# CPU_Module.net
KiCad netlist of a schematic drawn in Altium Designer
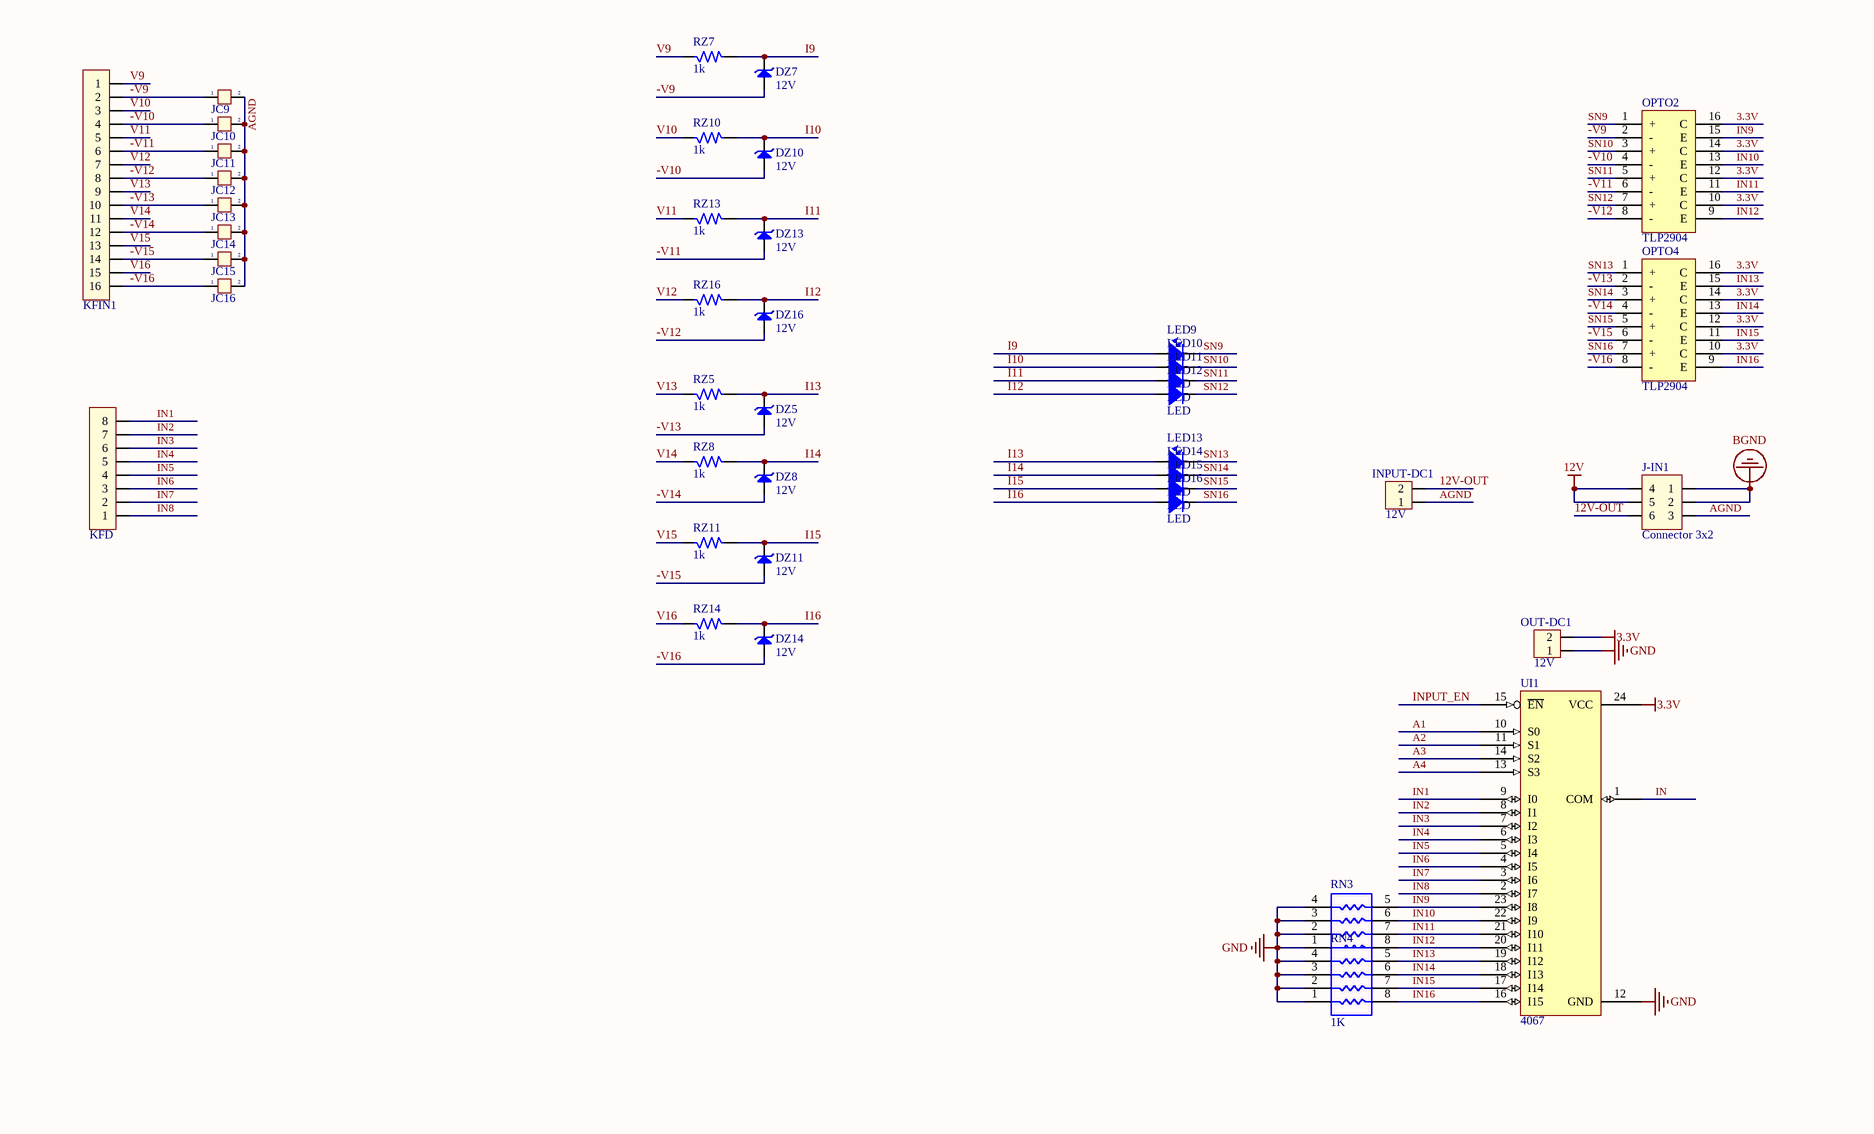
[diagram p0: CPU Module.SchDoc, top]
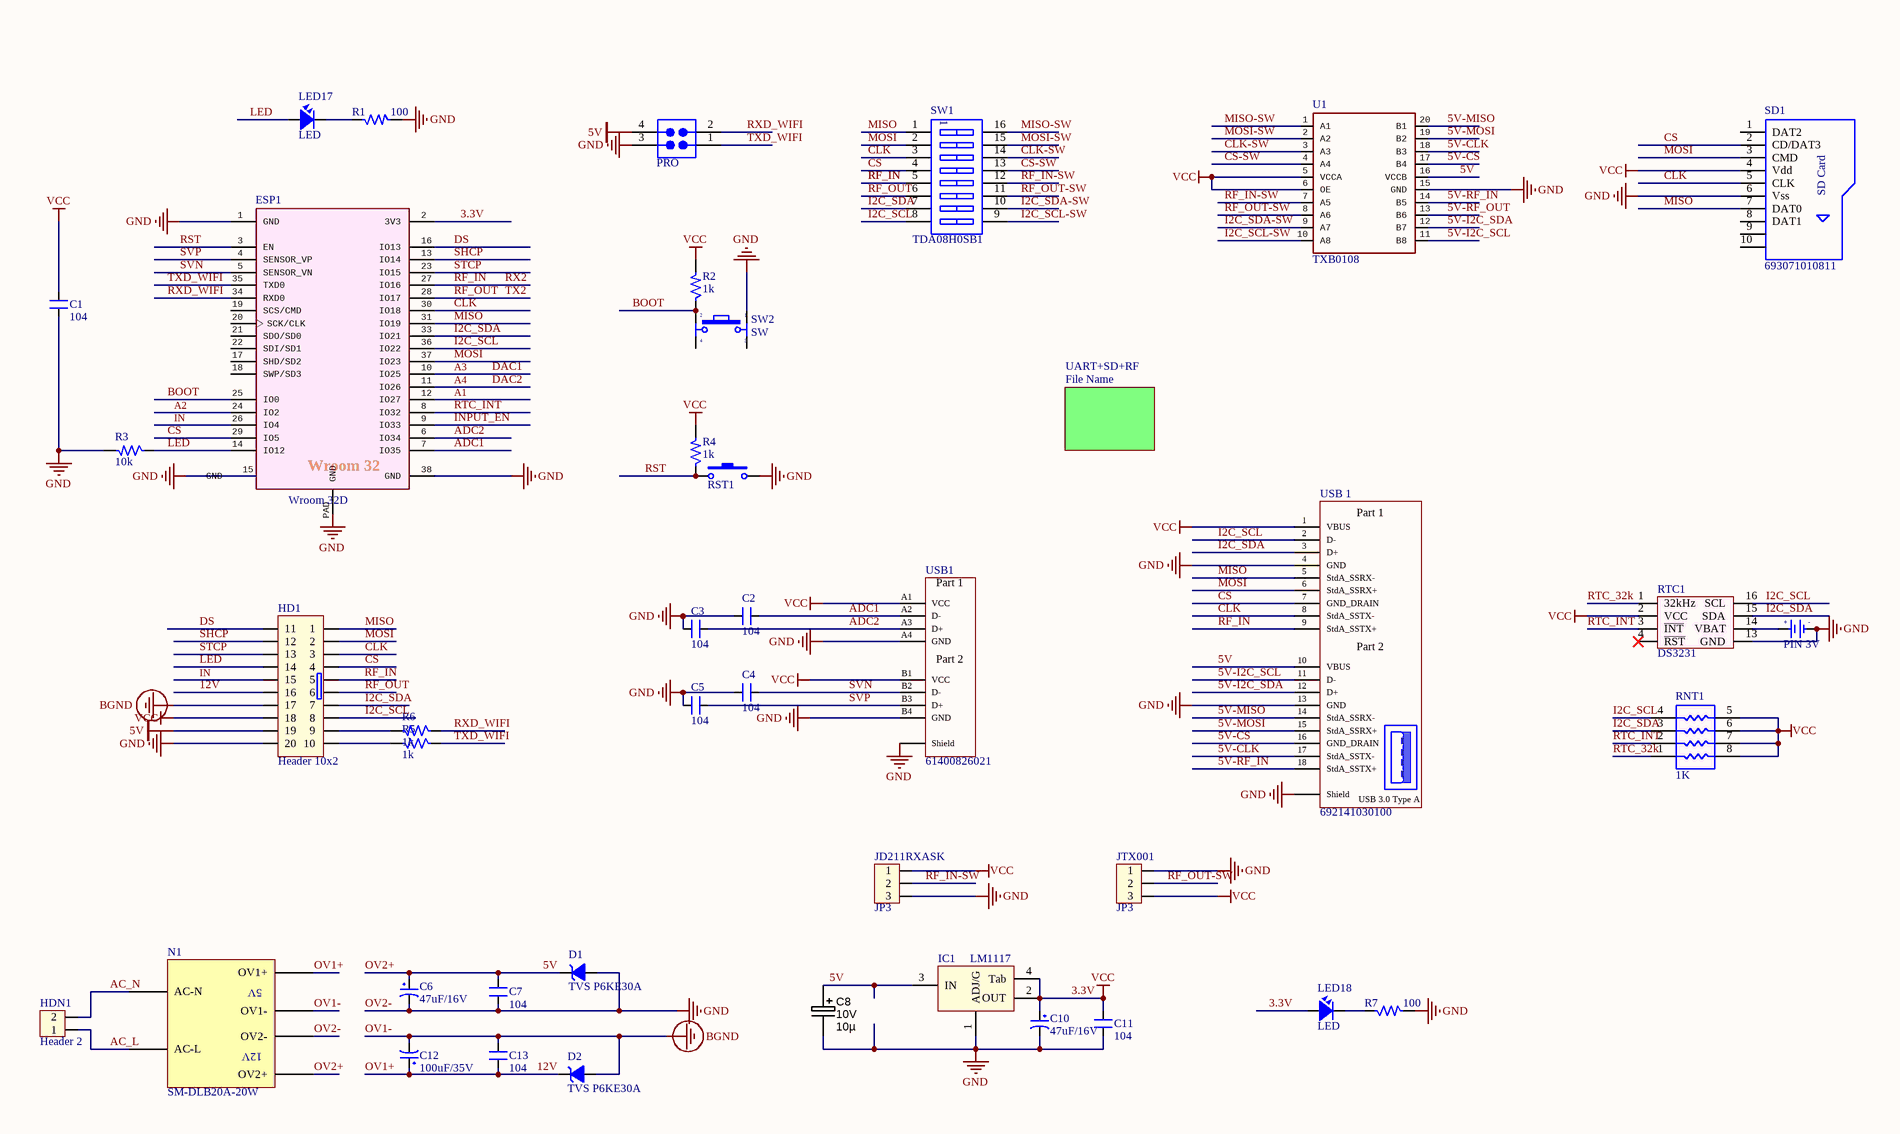
[diagram p1: CPU Module.SchDoc, bottom]

(export (version "E")
  (design (tool "Eeschema 10.0.6"))
  (components
    (comp (ref "BT1")
      (value "PIN 3V")
      (footprint "PIN CR1220-SMD")
      (description "Lithium Battery Holder for CR2032 3V Cell")
      (libsource (lib "Library") (part "PIN 3V"))
    )
    (comp (ref "C1")
      (value "104")
      (footprint "SM-0805")
      (description "Cap SMD")
      (libsource (lib "syhaunguyen") (part "CM"))
    )
    (comp (ref "C2")
      (value "104")
      (footprint "SM-0805")
      (description "Cap SMD")
      (libsource (lib "syhaunguyen") (part "CM"))
    )
    (comp (ref "C3")
      (value "104")
      (footprint "SM-0805")
      (description "Cap SMD")
      (libsource (lib "syhaunguyen") (part "CM"))
    )
    (comp (ref "C4")
      (value "104")
      (footprint "SM-0805")
      (description "Cap SMD")
      (libsource (lib "syhaunguyen") (part "CM"))
    )
    (comp (ref "C5")
      (value "104")
      (footprint "SM-0805")
      (description "Cap SMD")
      (libsource (lib "syhaunguyen") (part "CM"))
    )
    (comp (ref "C6")
      (value "47uF/16V")
      (footprint "WCAP-AS5H_6.3x5.5")
      (description "Cap 100uF/35V - 470uF/16V")
      (libsource (lib "syhaunguyen") (part "CP3"))
    )
    (comp (ref "C7")
      (value "104")
      (footprint "SM-0805")
      (description "Cap SMD")
      (libsource (lib "syhaunguyen") (part "CM"))
    )
    (comp (ref "C8")
      (value "10µ")
      (footprint "CAPMP3216X180N")
      (description "Capacitor SMD Tantalum 10uF 20% 10V 0805")
      (fields (field (name "TOLERANCE") "±20%") (field (name "RATINGS") "10V"))
      (libsource (lib "PBL - Capacitors") (part "CAPT_10u_0805_10V"))
    )
    (comp (ref "C10")
      (value "47uF/16V")
      (footprint "WCAP-AS5H_6.3x5.5")
      (description "Cap 100uF/35V - 470uF/16V")
      (libsource (lib "") (part "CP3_1"))
    )
    (comp (ref "C11")
      (value "104")
      (footprint "SM-0805")
      (description "Cap SMD")
      (libsource (lib "syhaunguyen") (part "CM"))
    )
    (comp (ref "C12")
      (value "100uF/35V")
      (footprint "WCAP-AS5H_8x10.5")
      (description "Cap 100uF/35V - 470uF/16V")
      (libsource (lib "syhaunguyen") (part "CP3"))
    )
    (comp (ref "C13")
      (value "104")
      (footprint "SM-0805")
      (description "Cap SMD")
      (libsource (lib "syhaunguyen") (part "CM"))
    )
    (comp (ref "D1")
      (value "TVS P6KE30A")
      (footprint "DO-214AA_Unidirectional")
      (description "Diode Zenner")
      (libsource (lib "syhaunguyen") (part "DZ"))
    )
    (comp (ref "D2")
      (value "TVS P6KE30A")
      (footprint "DO-214AA_Unidirectional")
      (description "Diode Zenner")
      (libsource (lib "syhaunguyen") (part "DZ"))
    )
    (comp (ref "DZ5")
      (value "12V")
      (footprint "DIOS 1S2P1406H")
      (description "DIODE GEN PURP 75V 200MA LLDS")
      (libsource (lib "Diode") (part "DIODE Zener"))
    )
    (comp (ref "DZ7")
      (value "12V")
      (footprint "DIOS 1S2P1406H")
      (description "DIODE GEN PURP 75V 200MA LLDS")
      (libsource (lib "Diode") (part "DIODE Zener"))
    )
    (comp (ref "DZ8")
      (value "12V")
      (footprint "DIOS 1S2P1406H")
      (description "DIODE GEN PURP 75V 200MA LLDS")
      (libsource (lib "Diode") (part "DIODE Zener"))
    )
    (comp (ref "DZ10")
      (value "12V")
      (footprint "DIOS 1S2P1406H")
      (description "DIODE GEN PURP 75V 200MA LLDS")
      (libsource (lib "Diode") (part "DIODE Zener"))
    )
    (comp (ref "DZ11")
      (value "12V")
      (footprint "DIOS 1S2P1406H")
      (description "DIODE GEN PURP 75V 200MA LLDS")
      (libsource (lib "Diode") (part "DIODE Zener"))
    )
    (comp (ref "DZ13")
      (value "12V")
      (footprint "DIOS 1S2P1406H")
      (description "DIODE GEN PURP 75V 200MA LLDS")
      (libsource (lib "Diode") (part "DIODE Zener"))
    )
    (comp (ref "DZ14")
      (value "12V")
      (footprint "DIOS 1S2P1406H")
      (description "DIODE GEN PURP 75V 200MA LLDS")
      (libsource (lib "Diode") (part "DIODE Zener"))
    )
    (comp (ref "DZ16")
      (value "12V")
      (footprint "DIOS 1S2P1406H")
      (description "DIODE GEN PURP 75V 200MA LLDS")
      (libsource (lib "Diode") (part "DIODE Zener"))
    )
    (comp (ref "ESP1")
      (value "Wroom 32D")
      (footprint "MODULE_ESP-WROOM-32")
      (fields (field (name "MF") "Olimex LTD") (field (name "MP") "ESP-WROOM-32"))
      (libsource (lib "ESP-WROOM-32") (part "ESP-WROOM-32"))
    )
    (comp (ref "HD1")
      (value "Header 10x2")
      (footprint "Hed2X10S")
      (libsource (lib "syhaunguyen") (part "HED10X2"))
    )
    (comp (ref "HDN1")
      (value "Header 2")
      (footprint "KF211V- 2")
      (description "Header 2 (Green)")
      (libsource (lib "syhaunguyen") (part "Hed2"))
    )
    (comp (ref "IC1")
      (value "LM1117")
      (footprint "SOT223-4N")
      (description "3v3")
      (libsource (lib "syhaunguyen") (part "LM1117"))
    )
    (comp (ref "INPUT-DC1")
      (value "12V")
      (footprint "KF211V- 2")
      (description "Header 2 (Green)")
      (libsource (lib "syhaunguyen") (part "Hed2"))
    )
    (comp (ref "J-IN1")
      (value "Connector 3x2")
      (footprint "JP3x2")
      (libsource (lib "syhaunguyen") (part "JP3x2"))
    )
    (comp (ref "JC9") (value "Jumper 2") (footprint "JP2") (libsource (lib "syhaunguyen") (part "JP 2")))
    (comp (ref "JC10") (value "Jumper 2") (footprint "JP2") (libsource (lib "syhaunguyen") (part "JP 2")))
    (comp (ref "JC11") (value "Jumper 2") (footprint "JP2") (libsource (lib "syhaunguyen") (part "JP 2")))
    (comp (ref "JC12") (value "Jumper 2") (footprint "JP2") (libsource (lib "syhaunguyen") (part "JP 2")))
    (comp (ref "JC13") (value "Jumper 2") (footprint "JP2") (libsource (lib "syhaunguyen") (part "JP 2")))
    (comp (ref "JC14") (value "Jumper 2") (footprint "JP2") (libsource (lib "syhaunguyen") (part "JP 2")))
    (comp (ref "JC15") (value "Jumper 2") (footprint "JP2") (libsource (lib "syhaunguyen") (part "JP 2")))
    (comp (ref "JC16") (value "Jumper 2") (footprint "JP2") (libsource (lib "syhaunguyen") (part "JP 2")))
    (comp (ref "JD211RXASK")
      (value "JP3")
      (footprint "JP3")
      (description "Connector 3")
      (libsource (lib "syhaunguyen") (part "Con3"))
    )
    (comp (ref "JTX001")
      (value "JP3")
      (footprint "JP3")
      (description "Connector 3")
      (libsource (lib "syhaunguyen") (part "Con3"))
    )
    (comp (ref "KFD")
      (value "Header 8")
      (footprint "KF211V- 8")
      (description "KF211R-5.0")
      (libsource (lib "Sonbui") (part "KF 8"))
    )
    (comp (ref "KFIN1")
      (value "Header 16")
      (footprint "KF211V- 16")
      (description "KF211R-5.0")
      (libsource (lib "Sonbui") (part "KF 16"))
    )
    (comp (ref "LED9")
      (value "LED")
      (footprint "LED0805")
      (description "LED Single colour Green and Red")
      (libsource (lib "syhaunguyen") (part "LED"))
    )
    (comp (ref "LED10")
      (value "LED")
      (footprint "LED0805")
      (description "LED Single colour Green and Red")
      (libsource (lib "syhaunguyen") (part "LED"))
    )
    (comp (ref "LED11")
      (value "LED")
      (footprint "LED0805")
      (description "LED Single colour Green and Red")
      (libsource (lib "syhaunguyen") (part "LED"))
    )
    (comp (ref "LED12")
      (value "LED")
      (footprint "LED0805")
      (description "LED Single colour Green and Red")
      (libsource (lib "syhaunguyen") (part "LED"))
    )
    (comp (ref "LED13")
      (value "LED")
      (footprint "LED0805")
      (description "LED Single colour Green and Red")
      (libsource (lib "syhaunguyen") (part "LED"))
    )
    (comp (ref "LED14")
      (value "LED")
      (footprint "LED0805")
      (description "LED Single colour Green and Red")
      (libsource (lib "syhaunguyen") (part "LED"))
    )
    (comp (ref "LED15")
      (value "LED")
      (footprint "LED0805")
      (description "LED Single colour Green and Red")
      (libsource (lib "syhaunguyen") (part "LED"))
    )
    (comp (ref "LED16")
      (value "LED")
      (footprint "LED0805")
      (description "LED Single colour Green and Red")
      (libsource (lib "syhaunguyen") (part "LED"))
    )
    (comp (ref "LED17")
      (value "LED")
      (footprint "LED0805")
      (description "LED Single colour Green and Red")
      (libsource (lib "syhaunguyen") (part "LED"))
    )
    (comp (ref "LED18")
      (value "LED")
      (footprint "LED0805")
      (description "LED Single colour Green and Red")
      (libsource (lib "syhaunguyen") (part "LED"))
    )
    (comp (ref "N1")
      (value "SM-DLB20A-20W")
      (footprint "SM-DLB20A")
      (libsource (lib "AC-DC Module") (part "SM-DLB20A-20W"))
    )
    (comp (ref "OPTO2")
      (value "TLP2904")
      (footprint "SO-16")
      (description "PC817 OPTO")
      (libsource (lib "Cty1") (part "PC817 x 4"))
    )
    (comp (ref "OPTO4")
      (value "TLP2904")
      (footprint "SO-16")
      (description "PC817 OPTO")
      (libsource (lib "Cty1") (part "PC817 x 4"))
    )
    (comp (ref "OUT-DC1")
      (value "12V")
      (footprint "KF211V- 2")
      (description "Header 2 (Green)")
      (libsource (lib "syhaunguyen") (part "Hed2"))
    )
    (comp (ref "PRO")
      (value "61300421821")
      (footprint "61300421121")
      (description "2.54 mm Dual Socket Header, 04p")
      (fields (field (name "PUBLISHER") "Wurth Elektronik"))
      (libsource (lib "JUMPER") (part "JP2x2 2.54MM"))
    )
    (comp (ref "R1")
      (value "100")
      (footprint "R-0805")
      (description "Resistor 1/4W")
      (libsource (lib "heromap") (part "R"))
    )
    (comp (ref "R2")
      (value "1k")
      (footprint "R-0805")
      (description "Resistor 1/4W")
      (libsource (lib "heromap") (part "R"))
    )
    (comp (ref "R3")
      (value "10k")
      (footprint "R-0805")
      (description "Resistor 1/4W")
      (libsource (lib "heromap") (part "R"))
    )
    (comp (ref "R4")
      (value "1k")
      (footprint "R-0805")
      (description "Resistor 1/4W")
      (libsource (lib "heromap") (part "R"))
    )
    (comp (ref "R5")
      (value "1k")
      (footprint "R-0805")
      (description "Resistor 1/4W")
      (libsource (lib "heromap") (part "R"))
    )
    (comp (ref "R6")
      (value "1k")
      (footprint "R-0805")
      (description "Resistor 1/4W")
      (libsource (lib "heromap") (part "R"))
    )
    (comp (ref "R7")
      (value "100")
      (footprint "R-0805")
      (description "Resistor 1/4W")
      (libsource (lib "heromap") (part "R"))
    )
    (comp (ref "RN3")
      (value "1K")
      (footprint "RES P4 Dual 0805/2012")
      (libsource (lib "Resistor") (part "Respack 4 Dual"))
    )
    (comp (ref "RN4")
      (value "1K")
      (footprint "RES P4 Dual 0805/2012")
      (libsource (lib "Resistor") (part "Respack 4 Dual"))
    )
    (comp (ref "RNT1")
      (value "1K")
      (footprint "RES P4 Dual 0805/2012")
      (libsource (lib "Resistor") (part "Respack 4 Dual"))
    )
    (comp (ref "RST1")
      (value "SW-SMD")
      (footprint "SW-SMD")
      (description "Switch")
      (fields (field (name "PUBLISHER") "Altium Limited"))
      (libsource (lib "Schematic") (part "SW-SMD"))
    )
    (comp (ref "RTC1")
      (value "DS3231")
      (footprint "SOIC127P750X1030-16N")
      (description "I2C RTC/TCXO/Crystal")
      (libsource (lib "Ics") (part "DS3231"))
    )
    (comp (ref "RZ5")
      (value "1k")
      (footprint "SM-1206")
      (description "Resistor 1/4W")
      (libsource (lib "syhaunguyen") (part "R"))
    )
    (comp (ref "RZ7")
      (value "1k")
      (footprint "SM-1206")
      (description "Resistor 1/4W")
      (libsource (lib "syhaunguyen") (part "R"))
    )
    (comp (ref "RZ8")
      (value "1k")
      (footprint "SM-1206")
      (description "Resistor 1/4W")
      (libsource (lib "syhaunguyen") (part "R"))
    )
    (comp (ref "RZ10")
      (value "1k")
      (footprint "SM-1206")
      (description "Resistor 1/4W")
      (libsource (lib "syhaunguyen") (part "R"))
    )
    (comp (ref "RZ11")
      (value "1k")
      (footprint "SM-1206")
      (description "Resistor 1/4W")
      (libsource (lib "syhaunguyen") (part "R"))
    )
    (comp (ref "RZ13")
      (value "1k")
      (footprint "SM-1206")
      (description "Resistor 1/4W")
      (libsource (lib "syhaunguyen") (part "R"))
    )
    (comp (ref "RZ14")
      (value "1k")
      (footprint "SM-1206")
      (description "Resistor 1/4W")
      (libsource (lib "syhaunguyen") (part "R"))
    )
    (comp (ref "RZ16")
      (value "1k")
      (footprint "SM-1206")
      (description "Resistor 1/4W")
      (libsource (lib "syhaunguyen") (part "R"))
    )
    (comp (ref "SD1")
      (value "693071010811")
      (footprint "693071010811")
      (description "Micro SD Card Connector Push & Push - 8 pins")
      (fields (field (name "PUBLISHER") "Wurth Elektronik"))
      (libsource (lib "Card") (part "SD-693071010811"))
    )
    (comp (ref "SW1")
      (value "TDA08H0SB1")
      (footprint "SW8-416131160808")
      (description "WS-DITV 2.54 mm small compact THT with raised actuator, 8p")
      (fields (field (name "PART NUMBER") "418127270908") (field (name "PUBLISHER") "Wurth Elektronik"))
      (libsource (lib "Switch") (part "SW 8P"))
    )
    (comp (ref "SW2")
      (value "SW")
      (footprint "SW2-D2")
      (description "Switch button 4 pin")
      (libsource (lib "ESP8266_CD4051") (part "SW4"))
    )
    (comp (ref "U1")
      (value "TXB0108")
      (footprint "TSSOP65P440X650-20N")
      (fields (field (name "MF") "Texas Instruments"))
      (libsource (lib "TXB0108") (part "TXB0108"))
    )
    (comp (ref "UI1")
      (value "4067")
      (footprint "SSOP65P530X850-24N")
      (description "MUX-74HC4067")
      (libsource (lib "CustomLibrary") (part "MUX-74HC4067"))
    )
    (comp (ref "USB 1")
      (value "692141030100")
      (footprint "692141030100")
      (description "USB 3.0 Type A")
      (fields (field (name "PUBLISHER") "Wurth Elektronik"))
      (libsource (lib "Usb") (part "USB 3.0 Type A Female THR Stacked"))
    )
    (comp (ref "USB1")
      (value "61400826021")
      (footprint "61400826021")
      (description "USB 2.0 Type A Female THR Stacked")
      (fields (field (name "PUBLISHER") "Wurth Elektronik"))
      (libsource (lib "Usb") (part "USB 2.0 Type A Female THR Stacked"))
    )
  )
  (nets
    (net (code "1") (name "/-V9") (class "Default")
      (node (ref "DZ7") (pin "1") (pinfunction "A_1") (pintype "passive"))
      (node (ref "JC9") (pin "1") (pinfunction "1_1") (pintype "passive"))
      (node (ref "KFIN1") (pin "2") (pinfunction "2_2") (pintype "passive"))
      (node (ref "OPTO2") (pin "2") (pinfunction "-_2") (pintype "passive"))
    )
    (net (code "2") (name "/-V10") (class "Default")
      (node (ref "DZ10") (pin "1") (pinfunction "A_1") (pintype "passive"))
      (node (ref "JC10") (pin "1") (pinfunction "1_1") (pintype "passive"))
      (node (ref "KFIN1") (pin "4") (pinfunction "4_4") (pintype "passive"))
      (node (ref "OPTO2") (pin "4") (pinfunction "-_4") (pintype "passive"))
    )
    (net (code "3") (name "/-V11") (class "Default")
      (node (ref "DZ13") (pin "1") (pinfunction "A_1") (pintype "passive"))
      (node (ref "JC11") (pin "1") (pinfunction "1_1") (pintype "passive"))
      (node (ref "KFIN1") (pin "6") (pinfunction "6_6") (pintype "passive"))
      (node (ref "OPTO2") (pin "6") (pinfunction "-_6") (pintype "passive"))
    )
    (net (code "4") (name "/-V12") (class "Default")
      (node (ref "DZ16") (pin "1") (pinfunction "A_1") (pintype "passive"))
      (node (ref "JC12") (pin "1") (pinfunction "1_1") (pintype "passive"))
      (node (ref "KFIN1") (pin "8") (pinfunction "8_8") (pintype "passive"))
      (node (ref "OPTO2") (pin "8") (pinfunction "-_8") (pintype "passive"))
    )
    (net (code "5") (name "/-V13") (class "Default")
      (node (ref "DZ5") (pin "1") (pinfunction "A_1") (pintype "passive"))
      (node (ref "JC13") (pin "1") (pinfunction "1_1") (pintype "passive"))
      (node (ref "KFIN1") (pin "10") (pinfunction "10_10") (pintype "passive"))
      (node (ref "OPTO4") (pin "2") (pinfunction "-_2") (pintype "passive"))
    )
    (net (code "6") (name "/-V14") (class "Default")
      (node (ref "DZ8") (pin "1") (pinfunction "A_1") (pintype "passive"))
      (node (ref "JC14") (pin "1") (pinfunction "1_1") (pintype "passive"))
      (node (ref "KFIN1") (pin "12") (pinfunction "12_12") (pintype "passive"))
      (node (ref "OPTO4") (pin "4") (pinfunction "-_4") (pintype "passive"))
    )
    (net (code "7") (name "/-V15") (class "Default")
      (node (ref "DZ11") (pin "1") (pinfunction "A_1") (pintype "passive"))
      (node (ref "JC15") (pin "1") (pinfunction "1_1") (pintype "passive"))
      (node (ref "KFIN1") (pin "14") (pinfunction "14_14") (pintype "passive"))
      (node (ref "OPTO4") (pin "6") (pinfunction "-_6") (pintype "passive"))
    )
    (net (code "8") (name "/-V16") (class "Default")
      (node (ref "DZ14") (pin "1") (pinfunction "A_1") (pintype "passive"))
      (node (ref "JC16") (pin "1") (pinfunction "1_1") (pintype "passive"))
      (node (ref "KFIN1") (pin "16") (pinfunction "16_16") (pintype "passive"))
      (node (ref "OPTO4") (pin "8") (pinfunction "-_8") (pintype "passive"))
    )
    (net (code "9") (name "/5V-CLK") (class "Default")
      (node (ref "U1") (pin "18") (pinfunction "B3_18") (pintype "passive"))
      (node (ref "USB 1") (pin "17") (pinfunction "StdA_SSTX-_17") (pintype "passive"))
    )
    (net (code "10") (name "/5V-CS") (class "Default")
      (node (ref "U1") (pin "17") (pinfunction "B4_17") (pintype "passive"))
      (node (ref "USB 1") (pin "16") (pinfunction "GND_DRAIN_16") (pintype "passive"))
    )
    (net (code "11") (name "/5V-I2C_SCL") (class "Default")
      (node (ref "U1") (pin "11") (pinfunction "B8_11") (pintype "passive"))
      (node (ref "USB 1") (pin "11") (pinfunction "D-_11") (pintype "passive"))
    )
    (net (code "12") (name "/5V-I2C_SDA") (class "Default")
      (node (ref "U1") (pin "12") (pinfunction "B7_12") (pintype "passive"))
      (node (ref "USB 1") (pin "12") (pinfunction "D+_12") (pintype "passive"))
    )
    (net (code "13") (name "/5V-MISO") (class "Default")
      (node (ref "U1") (pin "20") (pinfunction "B1_20") (pintype "passive"))
      (node (ref "USB 1") (pin "14") (pinfunction "StdA_SSRX-_14") (pintype "passive"))
    )
    (net (code "14") (name "/5V-MOSI") (class "Default")
      (node (ref "U1") (pin "19") (pinfunction "B2_19") (pintype "passive"))
      (node (ref "USB 1") (pin "15") (pinfunction "StdA_SSRX+_15") (pintype "passive"))
    )
    (net (code "15") (name "/5V-RF_IN") (class "Default")
      (node (ref "U1") (pin "14") (pinfunction "B5_14") (pintype "passive"))
      (node (ref "USB 1") (pin "18") (pinfunction "StdA_SSTX+_18") (pintype "passive"))
    )
    (net (code "16") (name "/5V-RF_OUT") (class "Default")
      (node (ref "U1") (pin "13") (pinfunction "B6_13") (pintype "passive"))
    )
    (net (code "17") (name "/12V-OUT") (class "Default")
      (node (ref "INPUT-DC1") (pin "2") (pinfunction "2_2") (pintype "passive"))
      (node (ref "J-IN1") (pin "6") (pinfunction "6_6") (pintype "passive"))
    )
    (net (code "18") (name "/A1") (class "Default")
      (node (ref "ESP1") (pin "12") (pinfunction "IO27_12") (pintype "passive"))
      (node (ref "UI1") (pin "10") (pinfunction "S0_10") (pintype "input"))
    )
    (net (code "19") (name "/A2") (class "Default")
      (node (ref "ESP1") (pin "24") (pinfunction "IO2_24") (pintype "passive"))
      (node (ref "UI1") (pin "11") (pinfunction "S1_11") (pintype "input"))
    )
    (net (code "20") (name "/A3") (class "Default")
      (node (ref "ESP1") (pin "10") (pinfunction "IO25_10") (pintype "passive"))
      (node (ref "UI1") (pin "14") (pinfunction "S2_14") (pintype "input"))
    )
    (net (code "21") (name "/A4") (class "Default")
      (node (ref "ESP1") (pin "11") (pinfunction "IO26_11") (pintype "passive"))
      (node (ref "UI1") (pin "13") (pinfunction "S3_13") (pintype "input"))
    )
    (net (code "22") (name "/AC_L") (class "Default")
      (node (ref "HDN1") (pin "1") (pinfunction "1_1") (pintype "passive"))
      (node (ref "N1") (pin "AC-L") (pinfunction "AC-L_AC-L") (pintype "passive"))
    )
    (net (code "23") (name "/AC_N") (class "Default")
      (node (ref "HDN1") (pin "2") (pinfunction "2_2") (pintype "passive"))
      (node (ref "N1") (pin "AC-N") (pinfunction "AC-N_AC-N") (pintype "passive"))
    )
    (net (code "24") (name "/ADC1") (class "Default")
      (node (ref "C2") (pin "1") (pinfunction "1_1") (pintype "passive"))
      (node (ref "ESP1") (pin "7") (pinfunction "IO35_7") (pintype "passive"))
      (node (ref "USB1") (pin "A2") (pinfunction "D-_A2") (pintype "passive"))
    )
    (net (code "25") (name "/ADC2") (class "Default")
      (node (ref "C3") (pin "2") (pinfunction "2_2") (pintype "passive"))
      (node (ref "ESP1") (pin "6") (pinfunction "IO34_6") (pintype "passive"))
      (node (ref "USB1") (pin "A3") (pinfunction "D+_A3") (pintype "passive"))
    )
    (net (code "26") (name "/AGND") (class "Default")
      (node (ref "INPUT-DC1") (pin "1") (pinfunction "1_1") (pintype "passive"))
      (node (ref "J-IN1") (pin "3") (pinfunction "3_3") (pintype "passive"))
      (node (ref "JC10") (pin "2") (pinfunction "2_2") (pintype "passive"))
      (node (ref "JC11") (pin "2") (pinfunction "2_2") (pintype "passive"))
      (node (ref "JC12") (pin "2") (pinfunction "2_2") (pintype "passive"))
      (node (ref "JC13") (pin "2") (pinfunction "2_2") (pintype "passive"))
      (node (ref "JC14") (pin "2") (pinfunction "2_2") (pintype "passive"))
      (node (ref "JC15") (pin "2") (pinfunction "2_2") (pintype "passive"))
      (node (ref "JC16") (pin "2") (pinfunction "2_2") (pintype "passive"))
      (node (ref "JC9") (pin "2") (pinfunction "2_2") (pintype "passive"))
    )
    (net (code "27") (name "/BOOT") (class "Default")
      (node (ref "ESP1") (pin "25") (pinfunction "IO0_25") (pintype "passive"))
      (node (ref "R2") (pin "1") (pinfunction "1_1") (pintype "passive"))
      (node (ref "SW2") (pin "2") (pinfunction "2_2") (pintype "passive"))
    )
    (net (code "28") (name "/CLK") (class "Default")
      (node (ref "ESP1") (pin "30") (pinfunction "IO18_30") (pintype "passive"))
      (node (ref "HD1") (pin "3") (pinfunction "3_3") (pintype "passive"))
      (node (ref "SD1") (pin "5") (pinfunction "CLK_5") (pintype "passive"))
      (node (ref "SW1") (pin "3") (pinfunction "3_3") (pintype "passive"))
      (node (ref "USB 1") (pin "8") (pinfunction "StdA_SSTX-_8") (pintype "passive"))
    )
    (net (code "29") (name "/CLK-SW") (class "Default")
      (node (ref "SW1") (pin "14") (pinfunction "14_14") (pintype "passive"))
      (node (ref "U1") (pin "3") (pinfunction "A3_3") (pintype "passive"))
    )
    (net (code "30") (name "/CS") (class "Default")
      (node (ref "ESP1") (pin "29") (pinfunction "IO5_29") (pintype "passive"))
      (node (ref "HD1") (pin "4") (pinfunction "4_4") (pintype "passive"))
      (node (ref "SD1") (pin "2") (pinfunction "CD/DAT3_2") (pintype "passive"))
      (node (ref "SW1") (pin "4") (pinfunction "4_4") (pintype "passive"))
      (node (ref "USB 1") (pin "7") (pinfunction "GND_DRAIN_7") (pintype "passive"))
    )
    (net (code "31") (name "/CS-SW") (class "Default")
      (node (ref "SW1") (pin "13") (pinfunction "13_13") (pintype "passive"))
      (node (ref "U1") (pin "4") (pinfunction "A4_4") (pintype "passive"))
    )
    (net (code "32") (name "/DS") (class "Default")
      (node (ref "ESP1") (pin "16") (pinfunction "IO13_16") (pintype "passive"))
      (node (ref "HD1") (pin "11") (pinfunction "11_11") (pintype "passive"))
    )
    (net (code "33") (name "/I2C_SCL") (class "Default")
      (node (ref "ESP1") (pin "36") (pinfunction "IO22_36") (pintype "passive"))
      (node (ref "HD1") (pin "8") (pinfunction "8_8") (pintype "passive"))
      (node (ref "RNT1") (pin "4") (pinfunction "4_4") (pintype "passive"))
      (node (ref "RTC1") (pin "16") (pinfunction "SCL_16") (pintype "passive"))
      (node (ref "SW1") (pin "8") (pinfunction "8_8") (pintype "passive"))
      (node (ref "USB 1") (pin "2") (pinfunction "D-_2") (pintype "passive"))
    )
    (net (code "34") (name "/I2C_SCL-SW") (class "Default")
      (node (ref "SW1") (pin "9") (pinfunction "9_9") (pintype "passive"))
      (node (ref "U1") (pin "10") (pinfunction "A8_10") (pintype "passive"))
    )
    (net (code "35") (name "/I2C_SDA") (class "Default")
      (node (ref "ESP1") (pin "33") (pinfunction "IO21_33") (pintype "passive"))
      (node (ref "HD1") (pin "7") (pinfunction "7_7") (pintype "passive"))
      (node (ref "RNT1") (pin "3") (pinfunction "3_3") (pintype "passive"))
      (node (ref "RTC1") (pin "15") (pinfunction "SDA_15") (pintype "passive"))
      (node (ref "SW1") (pin "7") (pinfunction "7_7") (pintype "passive"))
      (node (ref "USB 1") (pin "3") (pinfunction "D+_3") (pintype "passive"))
    )
    (net (code "36") (name "/I2C_SDA-SW") (class "Default")
      (node (ref "SW1") (pin "10") (pinfunction "10_10") (pintype "passive"))
      (node (ref "U1") (pin "9") (pinfunction "A7_9") (pintype "passive"))
    )
    (net (code "37") (name "/I9") (class "Default")
      (node (ref "DZ7") (pin "2") (pinfunction "K_2") (pintype "passive"))
      (node (ref "LED9") (pin "1") (pinfunction "1_1") (pintype "passive"))
      (node (ref "RZ7") (pin "2") (pinfunction "2_2") (pintype "passive"))
    )
    (net (code "38") (name "/I10") (class "Default")
      (node (ref "DZ10") (pin "2") (pinfunction "K_2") (pintype "passive"))
      (node (ref "LED10") (pin "1") (pinfunction "1_1") (pintype "passive"))
      (node (ref "RZ10") (pin "2") (pinfunction "2_2") (pintype "passive"))
    )
    (net (code "39") (name "/I11") (class "Default")
      (node (ref "DZ13") (pin "2") (pinfunction "K_2") (pintype "passive"))
      (node (ref "LED11") (pin "1") (pinfunction "1_1") (pintype "passive"))
      (node (ref "RZ13") (pin "2") (pinfunction "2_2") (pintype "passive"))
    )
    (net (code "40") (name "/I12") (class "Default")
      (node (ref "DZ16") (pin "2") (pinfunction "K_2") (pintype "passive"))
      (node (ref "LED12") (pin "1") (pinfunction "1_1") (pintype "passive"))
      (node (ref "RZ16") (pin "2") (pinfunction "2_2") (pintype "passive"))
    )
    (net (code "41") (name "/I13") (class "Default")
      (node (ref "DZ5") (pin "2") (pinfunction "K_2") (pintype "passive"))
      (node (ref "LED13") (pin "1") (pinfunction "1_1") (pintype "passive"))
      (node (ref "RZ5") (pin "2") (pinfunction "2_2") (pintype "passive"))
    )
    (net (code "42") (name "/I14") (class "Default")
      (node (ref "DZ8") (pin "2") (pinfunction "K_2") (pintype "passive"))
      (node (ref "LED14") (pin "1") (pinfunction "1_1") (pintype "passive"))
      (node (ref "RZ8") (pin "2") (pinfunction "2_2") (pintype "passive"))
    )
    (net (code "43") (name "/I15") (class "Default")
      (node (ref "DZ11") (pin "2") (pinfunction "K_2") (pintype "passive"))
      (node (ref "LED15") (pin "1") (pinfunction "1_1") (pintype "passive"))
      (node (ref "RZ11") (pin "2") (pinfunction "2_2") (pintype "passive"))
    )
    (net (code "44") (name "/I16") (class "Default")
      (node (ref "DZ14") (pin "2") (pinfunction "K_2") (pintype "passive"))
      (node (ref "LED16") (pin "1") (pinfunction "1_1") (pintype "passive"))
      (node (ref "RZ14") (pin "2") (pinfunction "2_2") (pintype "passive"))
    )
    (net (code "45") (name "/IN") (class "Default")
      (node (ref "ESP1") (pin "26") (pinfunction "IO4_26") (pintype "passive"))
      (node (ref "HD1") (pin "15") (pinfunction "15_15") (pintype "passive"))
      (node (ref "UI1") (pin "1") (pinfunction "COM_1") (pintype "bidirectional"))
    )
    (net (code "46") (name "/IN1") (class "Default")
      (node (ref "KFD") (pin "8") (pinfunction "8_8") (pintype "passive"))
      (node (ref "UI1") (pin "9") (pinfunction "I0_9") (pintype "bidirectional"))
    )
    (net (code "47") (name "/IN2") (class "Default")
      (node (ref "KFD") (pin "7") (pinfunction "7_7") (pintype "passive"))
      (node (ref "UI1") (pin "8") (pinfunction "I1_8") (pintype "bidirectional"))
    )
    (net (code "48") (name "/IN3") (class "Default")
      (node (ref "KFD") (pin "6") (pinfunction "6_6") (pintype "passive"))
      (node (ref "UI1") (pin "7") (pinfunction "I2_7") (pintype "bidirectional"))
    )
    (net (code "49") (name "/IN4") (class "Default")
      (node (ref "KFD") (pin "5") (pinfunction "5_5") (pintype "passive"))
      (node (ref "UI1") (pin "6") (pinfunction "I3_6") (pintype "bidirectional"))
    )
    (net (code "50") (name "/IN5") (class "Default")
      (node (ref "KFD") (pin "4") (pinfunction "4_4") (pintype "passive"))
      (node (ref "UI1") (pin "5") (pinfunction "I4_5") (pintype "bidirectional"))
    )
    (net (code "51") (name "/IN6") (class "Default")
      (node (ref "KFD") (pin "3") (pinfunction "3_3") (pintype "passive"))
      (node (ref "UI1") (pin "4") (pinfunction "I5_4") (pintype "bidirectional"))
    )
    (net (code "52") (name "/IN7") (class "Default")
      (node (ref "KFD") (pin "2") (pinfunction "2_2") (pintype "passive"))
      (node (ref "UI1") (pin "3") (pinfunction "I6_3") (pintype "bidirectional"))
    )
    (net (code "53") (name "/IN8") (class "Default")
      (node (ref "KFD") (pin "1") (pinfunction "1_1") (pintype "passive"))
      (node (ref "UI1") (pin "2") (pinfunction "I7_2") (pintype "bidirectional"))
    )
    (net (code "54") (name "/IN9") (class "Default")
      (node (ref "OPTO2") (pin "15") (pinfunction "E_15") (pintype "passive"))
      (node (ref "RN3") (pin "5") (pinfunction "5_5") (pintype "passive"))
      (node (ref "UI1") (pin "23") (pinfunction "I8_23") (pintype "bidirectional"))
    )
    (net (code "55") (name "/IN10") (class "Default")
      (node (ref "OPTO2") (pin "13") (pinfunction "E_13") (pintype "passive"))
      (node (ref "RN3") (pin "6") (pinfunction "6_6") (pintype "passive"))
      (node (ref "UI1") (pin "22") (pinfunction "I9_22") (pintype "bidirectional"))
    )
    (net (code "56") (name "/IN11") (class "Default")
      (node (ref "OPTO2") (pin "11") (pinfunction "E_11") (pintype "passive"))
      (node (ref "RN3") (pin "7") (pinfunction "7_7") (pintype "passive"))
      (node (ref "UI1") (pin "21") (pinfunction "I10_21") (pintype "bidirectional"))
    )
    (net (code "57") (name "/IN12") (class "Default")
      (node (ref "OPTO2") (pin "9") (pinfunction "E_9") (pintype "passive"))
      (node (ref "RN3") (pin "8") (pinfunction "8_8") (pintype "passive"))
      (node (ref "UI1") (pin "20") (pinfunction "I11_20") (pintype "bidirectional"))
    )
    (net (code "58") (name "/IN13") (class "Default")
      (node (ref "OPTO4") (pin "15") (pinfunction "E_15") (pintype "passive"))
      (node (ref "RN4") (pin "5") (pinfunction "5_5") (pintype "passive"))
      (node (ref "UI1") (pin "19") (pinfunction "I12_19") (pintype "bidirectional"))
    )
    (net (code "59") (name "/IN14") (class "Default")
      (node (ref "OPTO4") (pin "13") (pinfunction "E_13") (pintype "passive"))
      (node (ref "RN4") (pin "6") (pinfunction "6_6") (pintype "passive"))
      (node (ref "UI1") (pin "18") (pinfunction "I13_18") (pintype "bidirectional"))
    )
    (net (code "60") (name "/IN15") (class "Default")
      (node (ref "OPTO4") (pin "11") (pinfunction "E_11") (pintype "passive"))
      (node (ref "RN4") (pin "7") (pinfunction "7_7") (pintype "passive"))
      (node (ref "UI1") (pin "17") (pinfunction "I14_17") (pintype "bidirectional"))
    )
    (net (code "61") (name "/IN16") (class "Default")
      (node (ref "OPTO4") (pin "9") (pinfunction "E_9") (pintype "passive"))
      (node (ref "RN4") (pin "8") (pinfunction "8_8") (pintype "passive"))
      (node (ref "UI1") (pin "16") (pinfunction "I15_16") (pintype "bidirectional"))
    )
    (net (code "62") (name "/INPUT_EN") (class "Default")
      (node (ref "ESP1") (pin "9") (pinfunction "IO33_9") (pintype "passive"))
      (node (ref "UI1") (pin "15") (pinfunction "~{EN}_15") (pintype "input"))
    )
    (net (code "63") (name "/LED") (class "Default")
      (node (ref "ESP1") (pin "14") (pinfunction "IO12_14") (pintype "passive"))
      (node (ref "HD1") (pin "14") (pinfunction "14_14") (pintype "passive"))
      (node (ref "LED17") (pin "1") (pinfunction "1_1") (pintype "passive"))
      (node (ref "R3") (pin "1") (pinfunction "1_1") (pintype "passive"))
    )
    (net (code "64") (name "/MISO") (class "Default")
      (node (ref "ESP1") (pin "31") (pinfunction "IO19_31") (pintype "passive"))
      (node (ref "HD1") (pin "1") (pinfunction "1_1") (pintype "passive"))
      (node (ref "SD1") (pin "7") (pinfunction "DAT0_7") (pintype "passive"))
      (node (ref "SW1") (pin "1") (pinfunction "1_1") (pintype "passive"))
      (node (ref "USB 1") (pin "5") (pinfunction "StdA_SSRX-_5") (pintype "passive"))
    )
    (net (code "65") (name "/MISO-SW") (class "Default")
      (node (ref "SW1") (pin "16") (pinfunction "16_16") (pintype "passive"))
      (node (ref "U1") (pin "1") (pinfunction "A1_1") (pintype "passive"))
    )
    (net (code "66") (name "/MOSI") (class "Default")
      (node (ref "ESP1") (pin "37") (pinfunction "IO23_37") (pintype "passive"))
      (node (ref "HD1") (pin "2") (pinfunction "2_2") (pintype "passive"))
      (node (ref "SD1") (pin "3") (pinfunction "CMD_3") (pintype "passive"))
      (node (ref "SW1") (pin "2") (pinfunction "2_2") (pintype "passive"))
      (node (ref "USB 1") (pin "6") (pinfunction "StdA_SSRX+_6") (pintype "passive"))
    )
    (net (code "67") (name "/MOSI-SW") (class "Default")
      (node (ref "SW1") (pin "15") (pinfunction "15_15") (pintype "passive"))
      (node (ref "U1") (pin "2") (pinfunction "A2_2") (pintype "passive"))
    )
    (net (code "68") (name "/RF_IN") (class "Default")
      (node (ref "ESP1") (pin "27") (pinfunction "IO16_27") (pintype "passive"))
      (node (ref "HD1") (pin "5") (pinfunction "5_5") (pintype "passive"))
      (node (ref "SW1") (pin "5") (pinfunction "5_5") (pintype "passive"))
      (node (ref "USB 1") (pin "9") (pinfunction "StdA_SSTX+_9") (pintype "passive"))
    )
    (net (code "69") (name "/RF_IN-SW") (class "Default")
      (node (ref "JD211RXASK") (pin "2") (pinfunction "2_2") (pintype "passive"))
      (node (ref "SW1") (pin "12") (pinfunction "12_12") (pintype "passive"))
      (node (ref "U1") (pin "7") (pinfunction "A5_7") (pintype "passive"))
    )
    (net (code "70") (name "/RF_OUT") (class "Default")
      (node (ref "ESP1") (pin "28") (pinfunction "IO17_28") (pintype "passive"))
      (node (ref "HD1") (pin "6") (pinfunction "6_6") (pintype "passive"))
      (node (ref "SW1") (pin "6") (pinfunction "6_6") (pintype "passive"))
    )
    (net (code "71") (name "/RF_OUT-SW") (class "Default")
      (node (ref "JTX001") (pin "2") (pinfunction "2_2") (pintype "passive"))
      (node (ref "SW1") (pin "11") (pinfunction "11_11") (pintype "passive"))
      (node (ref "U1") (pin "8") (pinfunction "A6_8") (pintype "passive"))
    )
    (net (code "72") (name "/RST") (class "Default")
      (node (ref "ESP1") (pin "3") (pinfunction "EN_3") (pintype "passive"))
      (node (ref "R4") (pin "1") (pinfunction "1_1") (pintype "passive"))
      (node (ref "RST1") (pin "1") (pinfunction "1_1") (pintype "passive"))
    )
    (net (code "73") (name "/RTC_32k") (class "Default")
      (node (ref "RNT1") (pin "1") (pinfunction "1_1") (pintype "passive"))
      (node (ref "RTC1") (pin "1") (pinfunction "32kHz_1") (pintype "passive"))
    )
    (net (code "74") (name "/RTC_INT") (class "Default")
      (node (ref "ESP1") (pin "8") (pinfunction "IO32_8") (pintype "passive"))
      (node (ref "RNT1") (pin "2") (pinfunction "2_2") (pintype "passive"))
      (node (ref "RTC1") (pin "3") (pinfunction "~{INT}_3") (pintype "passive"))
    )
    (net (code "75") (name "/RXD_WIFI") (class "Default")
      (node (ref "ESP1") (pin "34") (pinfunction "RXD0_34") (pintype "passive"))
      (node (ref "PRO") (pin "2") (pinfunction "2_2") (pintype "passive"))
      (node (ref "R6") (pin "1") (pinfunction "1_1") (pintype "passive"))
    )
    (net (code "76") (name "/SHCP") (class "Default")
      (node (ref "ESP1") (pin "13") (pinfunction "IO14_13") (pintype "passive"))
      (node (ref "HD1") (pin "12") (pinfunction "12_12") (pintype "passive"))
    )
    (net (code "77") (name "/SN9") (class "Default")
      (node (ref "LED9") (pin "2") (pinfunction "2_2") (pintype "passive"))
      (node (ref "OPTO2") (pin "1") (pinfunction "+_1") (pintype "passive"))
    )
    (net (code "78") (name "/SN10") (class "Default")
      (node (ref "LED10") (pin "2") (pinfunction "2_2") (pintype "passive"))
      (node (ref "OPTO2") (pin "3") (pinfunction "+_3") (pintype "passive"))
    )
    (net (code "79") (name "/SN11") (class "Default")
      (node (ref "LED11") (pin "2") (pinfunction "2_2") (pintype "passive"))
      (node (ref "OPTO2") (pin "5") (pinfunction "+_5") (pintype "passive"))
    )
    (net (code "80") (name "/SN12") (class "Default")
      (node (ref "LED12") (pin "2") (pinfunction "2_2") (pintype "passive"))
      (node (ref "OPTO2") (pin "7") (pinfunction "+_7") (pintype "passive"))
    )
    (net (code "81") (name "/SN13") (class "Default")
      (node (ref "LED13") (pin "2") (pinfunction "2_2") (pintype "passive"))
      (node (ref "OPTO4") (pin "1") (pinfunction "+_1") (pintype "passive"))
    )
    (net (code "82") (name "/SN14") (class "Default")
      (node (ref "LED14") (pin "2") (pinfunction "2_2") (pintype "passive"))
      (node (ref "OPTO4") (pin "3") (pinfunction "+_3") (pintype "passive"))
    )
    (net (code "83") (name "/SN15") (class "Default")
      (node (ref "LED15") (pin "2") (pinfunction "2_2") (pintype "passive"))
      (node (ref "OPTO4") (pin "5") (pinfunction "+_5") (pintype "passive"))
    )
    (net (code "84") (name "/SN16") (class "Default")
      (node (ref "LED16") (pin "2") (pinfunction "2_2") (pintype "passive"))
      (node (ref "OPTO4") (pin "7") (pinfunction "+_7") (pintype "passive"))
    )
    (net (code "85") (name "/STCP") (class "Default")
      (node (ref "ESP1") (pin "23") (pinfunction "IO15_23") (pintype "passive"))
      (node (ref "HD1") (pin "13") (pinfunction "13_13") (pintype "passive"))
    )
    (net (code "86") (name "/SVN") (class "Default")
      (node (ref "C4") (pin "1") (pinfunction "1_1") (pintype "passive"))
      (node (ref "ESP1") (pin "5") (pinfunction "SENSOR_VN_5") (pintype "passive"))
      (node (ref "USB1") (pin "B2") (pinfunction "D-_B2") (pintype "passive"))
    )
    (net (code "87") (name "/SVP") (class "Default")
      (node (ref "C5") (pin "2") (pinfunction "2_2") (pintype "passive"))
      (node (ref "ESP1") (pin "4") (pinfunction "SENSOR_VP_4") (pintype "passive"))
      (node (ref "USB1") (pin "B3") (pinfunction "D+_B3") (pintype "passive"))
    )
    (net (code "88") (name "/TXD_WIFI") (class "Default")
      (node (ref "ESP1") (pin "35") (pinfunction "TXD0_35") (pintype "passive"))
      (node (ref "PRO") (pin "1") (pinfunction "1_1") (pintype "passive"))
      (node (ref "R5") (pin "1") (pinfunction "1_1") (pintype "passive"))
    )
    (net (code "89") (name "/V9") (class "Default")
      (node (ref "KFIN1") (pin "1") (pinfunction "1_1") (pintype "passive"))
      (node (ref "RZ7") (pin "1") (pinfunction "1_1") (pintype "passive"))
    )
    (net (code "90") (name "/V10") (class "Default")
      (node (ref "KFIN1") (pin "3") (pinfunction "3_3") (pintype "passive"))
      (node (ref "RZ10") (pin "1") (pinfunction "1_1") (pintype "passive"))
    )
    (net (code "91") (name "/V11") (class "Default")
      (node (ref "KFIN1") (pin "5") (pinfunction "5_5") (pintype "passive"))
      (node (ref "RZ13") (pin "1") (pinfunction "1_1") (pintype "passive"))
    )
    (net (code "92") (name "/V12") (class "Default")
      (node (ref "KFIN1") (pin "7") (pinfunction "7_7") (pintype "passive"))
      (node (ref "RZ16") (pin "1") (pinfunction "1_1") (pintype "passive"))
    )
    (net (code "93") (name "/V13") (class "Default")
      (node (ref "KFIN1") (pin "9") (pinfunction "9_9") (pintype "passive"))
      (node (ref "RZ5") (pin "1") (pinfunction "1_1") (pintype "passive"))
    )
    (net (code "94") (name "/V14") (class "Default")
      (node (ref "KFIN1") (pin "11") (pinfunction "11_11") (pintype "passive"))
      (node (ref "RZ8") (pin "1") (pinfunction "1_1") (pintype "passive"))
    )
    (net (code "95") (name "/V15") (class "Default")
      (node (ref "KFIN1") (pin "13") (pinfunction "13_13") (pintype "passive"))
      (node (ref "RZ11") (pin "1") (pinfunction "1_1") (pintype "passive"))
    )
    (net (code "96") (name "/V16") (class "Default")
      (node (ref "KFIN1") (pin "15") (pinfunction "15_15") (pintype "passive"))
      (node (ref "RZ14") (pin "1") (pinfunction "1_1") (pintype "passive"))
    )
    (net (code "97") (name "3.3V") (class "Default")
      (node (ref "C1") (pin "2") (pinfunction "2_2") (pintype "passive"))
      (node (ref "C10") (pin "1") (pinfunction "1_1") (pintype "passive"))
      (node (ref "C11") (pin "2") (pinfunction "2_2") (pintype "passive"))
      (node (ref "ESP1") (pin "2") (pinfunction "3V3_2") (pintype "power_in"))
      (node (ref "HD1") (pin "18") (pinfunction "18_18") (pintype "passive"))
      (node (ref "IC1") (pin "2") (pinfunction "OUT_2") (pintype "passive"))
      (node (ref "IC1") (pin "4") (pinfunction "Tab_4") (pintype "passive"))
      (node (ref "JD211RXASK") (pin "1") (pinfunction "1_1") (pintype "passive"))
      (node (ref "JTX001") (pin "3") (pinfunction "3_3") (pintype "passive"))
      (node (ref "LED18") (pin "1") (pinfunction "1_1") (pintype "passive"))
      (node (ref "OPTO2") (pin "10") (pinfunction "C_10") (pintype "passive"))
      (node (ref "OPTO2") (pin "12") (pinfunction "C_12") (pintype "passive"))
      (node (ref "OPTO2") (pin "14") (pinfunction "C_14") (pintype "passive"))
      (node (ref "OPTO2") (pin "16") (pinfunction "C_16") (pintype "passive"))
      (node (ref "OPTO4") (pin "10") (pinfunction "C_10") (pintype "passive"))
      (node (ref "OPTO4") (pin "12") (pinfunction "C_12") (pintype "passive"))
      (node (ref "OPTO4") (pin "14") (pinfunction "C_14") (pintype "passive"))
      (node (ref "OPTO4") (pin "16") (pinfunction "C_16") (pintype "passive"))
      (node (ref "OUT-DC1") (pin "2") (pinfunction "2_2") (pintype "passive"))
      (node (ref "R2") (pin "2") (pinfunction "2_2") (pintype "passive"))
      (node (ref "R4") (pin "2") (pinfunction "2_2") (pintype "passive"))
      (node (ref "RNT1") (pin "5") (pinfunction "5_5") (pintype "passive"))
      (node (ref "RNT1") (pin "6") (pinfunction "6_6") (pintype "passive"))
      (node (ref "RNT1") (pin "7") (pinfunction "7_7") (pintype "passive"))
      (node (ref "RNT1") (pin "8") (pinfunction "8_8") (pintype "passive"))
      (node (ref "RTC1") (pin "2") (pinfunction "VCC_2") (pintype "passive"))
      (node (ref "SD1") (pin "4") (pinfunction "Vdd_4") (pintype "passive"))
      (node (ref "U1") (pin "5") (pinfunction "VCCA_5") (pintype "passive"))
      (node (ref "U1") (pin "6") (pinfunction "OE_6") (pintype "passive"))
      (node (ref "UI1") (pin "24") (pinfunction "VCC_24") (pintype "power_in"))
      (node (ref "USB 1") (pin "1") (pinfunction "VBUS_1") (pintype "passive"))
      (node (ref "USB1") (pin "A1") (pinfunction "VCC_A1") (pintype "passive"))
      (node (ref "USB1") (pin "B1") (pinfunction "VCC_B1") (pintype "passive"))
    )
    (net (code "98") (name "5V") (class "Default")
      (node (ref "C6") (pin "1") (pinfunction "1_1") (pintype "passive"))
      (node (ref "C7") (pin "1") (pinfunction "1_1") (pintype "passive"))
      (node (ref "C8") (pin "1") (pintype "passive"))
      (node (ref "D1") (pin "2") (pinfunction "K_2") (pintype "passive"))
      (node (ref "HD1") (pin "19") (pinfunction "19_19") (pintype "passive"))
      (node (ref "IC1") (pin "3") (pinfunction "IN_3") (pintype "passive"))
      (node (ref "N1") (pin "OV2+") (pinfunction "OV2+_OV2+") (pintype "passive"))
      (node (ref "PRO") (pin "4") (pinfunction "4_4") (pintype "passive"))
      (node (ref "U1") (pin "16") (pinfunction "VCCB_16") (pintype "passive"))
      (node (ref "USB 1") (pin "10") (pinfunction "VBUS_10") (pintype "passive"))
    )
    (net (code "99") (name "12V") (class "Default")
      (node (ref "C12") (pin "1") (pinfunction "1_1") (pintype "passive"))
      (node (ref "C13") (pin "2") (pinfunction "2_2") (pintype "passive"))
      (node (ref "D2") (pin "2") (pinfunction "K_2") (pintype "passive"))
      (node (ref "HD1") (pin "16") (pinfunction "16_16") (pintype "passive"))
      (node (ref "J-IN1") (pin "4") (pinfunction "4_4") (pintype "passive"))
      (node (ref "J-IN1") (pin "5") (pinfunction "5_5") (pintype "passive"))
      (node (ref "N1") (pin "OV1+") (pinfunction "OV1+_OV1+") (pintype "passive"))
    )
    (net (code "100") (name "BGND") (class "Default")
      (node (ref "C12") (pin "2") (pinfunction "2_2") (pintype "passive"))
      (node (ref "C13") (pin "1") (pinfunction "1_1") (pintype "passive"))
      (node (ref "D2") (pin "1") (pinfunction "A_1") (pintype "passive"))
      (node (ref "HD1") (pin "17") (pinfunction "17_17") (pintype "passive"))
      (node (ref "J-IN1") (pin "1") (pinfunction "1_1") (pintype "passive"))
      (node (ref "J-IN1") (pin "2") (pinfunction "2_2") (pintype "passive"))
      (node (ref "N1") (pin "OV1-") (pinfunction "OV1-_OV1-") (pintype "passive"))
    )
    (net (code "101") (name "GND") (class "Default")
      (node (ref "BT1") (pin "2") (pinfunction "GND_2") (pintype "passive"))
      (node (ref "C1") (pin "1") (pinfunction "1_1") (pintype "passive"))
      (node (ref "C10") (pin "2") (pinfunction "2_2") (pintype "passive"))
      (node (ref "C11") (pin "1") (pinfunction "1_1") (pintype "passive"))
      (node (ref "C2") (pin "2") (pinfunction "2_2") (pintype "passive"))
      (node (ref "C3") (pin "1") (pinfunction "1_1") (pintype "passive"))
      (node (ref "C4") (pin "2") (pinfunction "2_2") (pintype "passive"))
      (node (ref "C5") (pin "1") (pinfunction "1_1") (pintype "passive"))
      (node (ref "C6") (pin "2") (pinfunction "2_2") (pintype "passive"))
      (node (ref "C7") (pin "2") (pinfunction "2_2") (pintype "passive"))
      (node (ref "C8") (pin "2") (pintype "passive"))
      (node (ref "D1") (pin "1") (pinfunction "A_1") (pintype "passive"))
      (node (ref "ESP1") (pin "1") (pinfunction "GND_1") (pintype "power_in"))
      (node (ref "ESP1") (pin "15") (pinfunction "GND_15") (pintype "power_in"))
      (node (ref "ESP1") (pin "38") (pinfunction "GND_38") (pintype "power_in"))
      (node (ref "ESP1") (pin "PAD") (pinfunction "GND_PAD") (pintype "power_in"))
      (node (ref "HD1") (pin "20") (pinfunction "20_20") (pintype "passive"))
      (node (ref "IC1") (pin "1") (pinfunction "ADJ/G_1") (pintype "passive"))
      (node (ref "JD211RXASK") (pin "3") (pinfunction "3_3") (pintype "passive"))
      (node (ref "JTX001") (pin "1") (pinfunction "1_1") (pintype "passive"))
      (node (ref "N1") (pin "OV2-") (pinfunction "OV2-_OV2-") (pintype "passive"))
      (node (ref "OUT-DC1") (pin "1") (pinfunction "1_1") (pintype "passive"))
      (node (ref "PRO") (pin "3") (pinfunction "3_3") (pintype "passive"))
      (node (ref "R1") (pin "2") (pinfunction "2_2") (pintype "passive"))
      (node (ref "R3") (pin "2") (pinfunction "2_2") (pintype "passive"))
      (node (ref "R7") (pin "2") (pinfunction "2_2") (pintype "passive"))
      (node (ref "RN3") (pin "1") (pinfunction "1_1") (pintype "passive"))
      (node (ref "RN3") (pin "2") (pinfunction "2_2") (pintype "passive"))
      (node (ref "RN3") (pin "3") (pinfunction "3_3") (pintype "passive"))
      (node (ref "RN3") (pin "4") (pinfunction "4_4") (pintype "passive"))
      (node (ref "RN4") (pin "1") (pinfunction "1_1") (pintype "passive"))
      (node (ref "RN4") (pin "2") (pinfunction "2_2") (pintype "passive"))
      (node (ref "RN4") (pin "3") (pinfunction "3_3") (pintype "passive"))
      (node (ref "RN4") (pin "4") (pinfunction "4_4") (pintype "passive"))
      (node (ref "RST1") (pin "2") (pinfunction "2_2") (pintype "passive"))
      (node (ref "RTC1") (pin "13") (pinfunction "GND_13") (pintype "passive"))
      (node (ref "SD1") (pin "6") (pinfunction "Vss_6") (pintype "passive"))
      (node (ref "SW2") (pin "1") (pinfunction "1_1") (pintype "passive"))
      (node (ref "U1") (pin "15") (pinfunction "GND_15") (pintype "passive"))
      (node (ref "UI1") (pin "12") (pinfunction "GND_12") (pintype "power_in"))
      (node (ref "USB 1") (pin "13") (pinfunction "GND_13") (pintype "passive"))
      (node (ref "USB 1") (pin "4") (pinfunction "GND_4") (pintype "passive"))
      (node (ref "USB 1") (pin "Shell") (pinfunction "Shield_Shell") (pintype "passive"))
      (node (ref "USB1") (pin "A4") (pinfunction "GND_A4") (pintype "passive"))
      (node (ref "USB1") (pin "B4") (pinfunction "GND_B4") (pintype "passive"))
      (node (ref "USB1") (pin "Shell") (pinfunction "Shield_Shell") (pintype "passive"))
    )
    (net (code "102") (name "Net-(BT1-+3V)") (class "Default")
      (node (ref "BT1") (pin "1") (pinfunction "+3V_1") (pintype "passive"))
      (node (ref "RTC1") (pin "14") (pinfunction "VBAT_14") (pintype "passive"))
    )
    (net (code "103") (name "Net-(HD1-Pad9)") (class "Default")
      (node (ref "HD1") (pin "9") (pinfunction "9_9") (pintype "passive"))
      (node (ref "R6") (pin "2") (pinfunction "2_2") (pintype "passive"))
    )
    (net (code "104") (name "Net-(HD1-Pad10)") (class "Default")
      (node (ref "HD1") (pin "10") (pinfunction "10_10") (pintype "passive"))
      (node (ref "R5") (pin "2") (pinfunction "2_2") (pintype "passive"))
    )
    (net (code "105") (name "Net-(LED17-Pad2)") (class "Default")
      (node (ref "LED17") (pin "2") (pinfunction "2_2") (pintype "passive"))
      (node (ref "R1") (pin "1") (pinfunction "1_1") (pintype "passive"))
    )
    (net (code "106") (name "Net-(LED18-Pad2)") (class "Default")
      (node (ref "LED18") (pin "2") (pinfunction "2_2") (pintype "passive"))
      (node (ref "R7") (pin "1") (pinfunction "1_1") (pintype "passive"))
    )
    (net (code "107") (name "unconnected-(ESP1-SCK{slash}CLK-Pad20)") (class "Default")
      (node (ref "ESP1") (pin "20") (pinfunction "SCK/CLK_20") (pintype "passive"))
    )
    (net (code "108") (name "unconnected-(ESP1-SCS{slash}CMD-Pad19)") (class "Default")
      (node (ref "ESP1") (pin "19") (pinfunction "SCS/CMD_19") (pintype "passive"))
    )
    (net (code "109") (name "unconnected-(ESP1-SDI{slash}SD1-Pad22)") (class "Default")
      (node (ref "ESP1") (pin "22") (pinfunction "SDI/SD1_22") (pintype "passive"))
    )
    (net (code "110") (name "unconnected-(ESP1-SDO{slash}SD0-Pad21)") (class "Default")
      (node (ref "ESP1") (pin "21") (pinfunction "SDO/SD0_21") (pintype "passive"))
    )
    (net (code "111") (name "unconnected-(ESP1-SHD{slash}SD2-Pad17)") (class "Default")
      (node (ref "ESP1") (pin "17") (pinfunction "SHD/SD2_17") (pintype "passive"))
    )
    (net (code "112") (name "unconnected-(ESP1-SWP{slash}SD3-Pad18)") (class "Default")
      (node (ref "ESP1") (pin "18") (pinfunction "SWP/SD3_18") (pintype "passive"))
    )
    (net (code "113") (name "unconnected-(RTC1-~{RST}-Pad4)") (class "Default")
      (node (ref "RTC1") (pin "4") (pinfunction "~{RST}_4") (pintype "passive+no_connect"))
    )
    (net (code "114") (name "unconnected-(SD1-DAT1-Pad8)") (class "Default")
      (node (ref "SD1") (pin "8") (pinfunction "DAT1_8") (pintype "passive"))
    )
    (net (code "115") (name "unconnected-(SD1-DAT2-Pad1)") (class "Default")
      (node (ref "SD1") (pin "1") (pinfunction "DAT2_1") (pintype "passive"))
    )
    (net (code "116") (name "unconnected-(SD1-Pad9)") (class "Default")
      (node (ref "SD1") (pin "9") (pinfunction "9_9") (pintype "passive"))
    )
    (net (code "117") (name "unconnected-(SD1-Pad10)") (class "Default")
      (node (ref "SD1") (pin "10") (pinfunction "10_10") (pintype "passive"))
    )
    (net (code "118") (name "unconnected-(SW2-Pad3)") (class "Default")
      (node (ref "SW2") (pin "3") (pinfunction "3_3") (pintype "passive"))
    )
    (net (code "119") (name "unconnected-(SW2-Pad4)") (class "Default")
      (node (ref "SW2") (pin "4") (pinfunction "4_4") (pintype "passive"))
    )
  )
)
